# other.net
KiCad netlist of a schematic drawn in Altium Designer
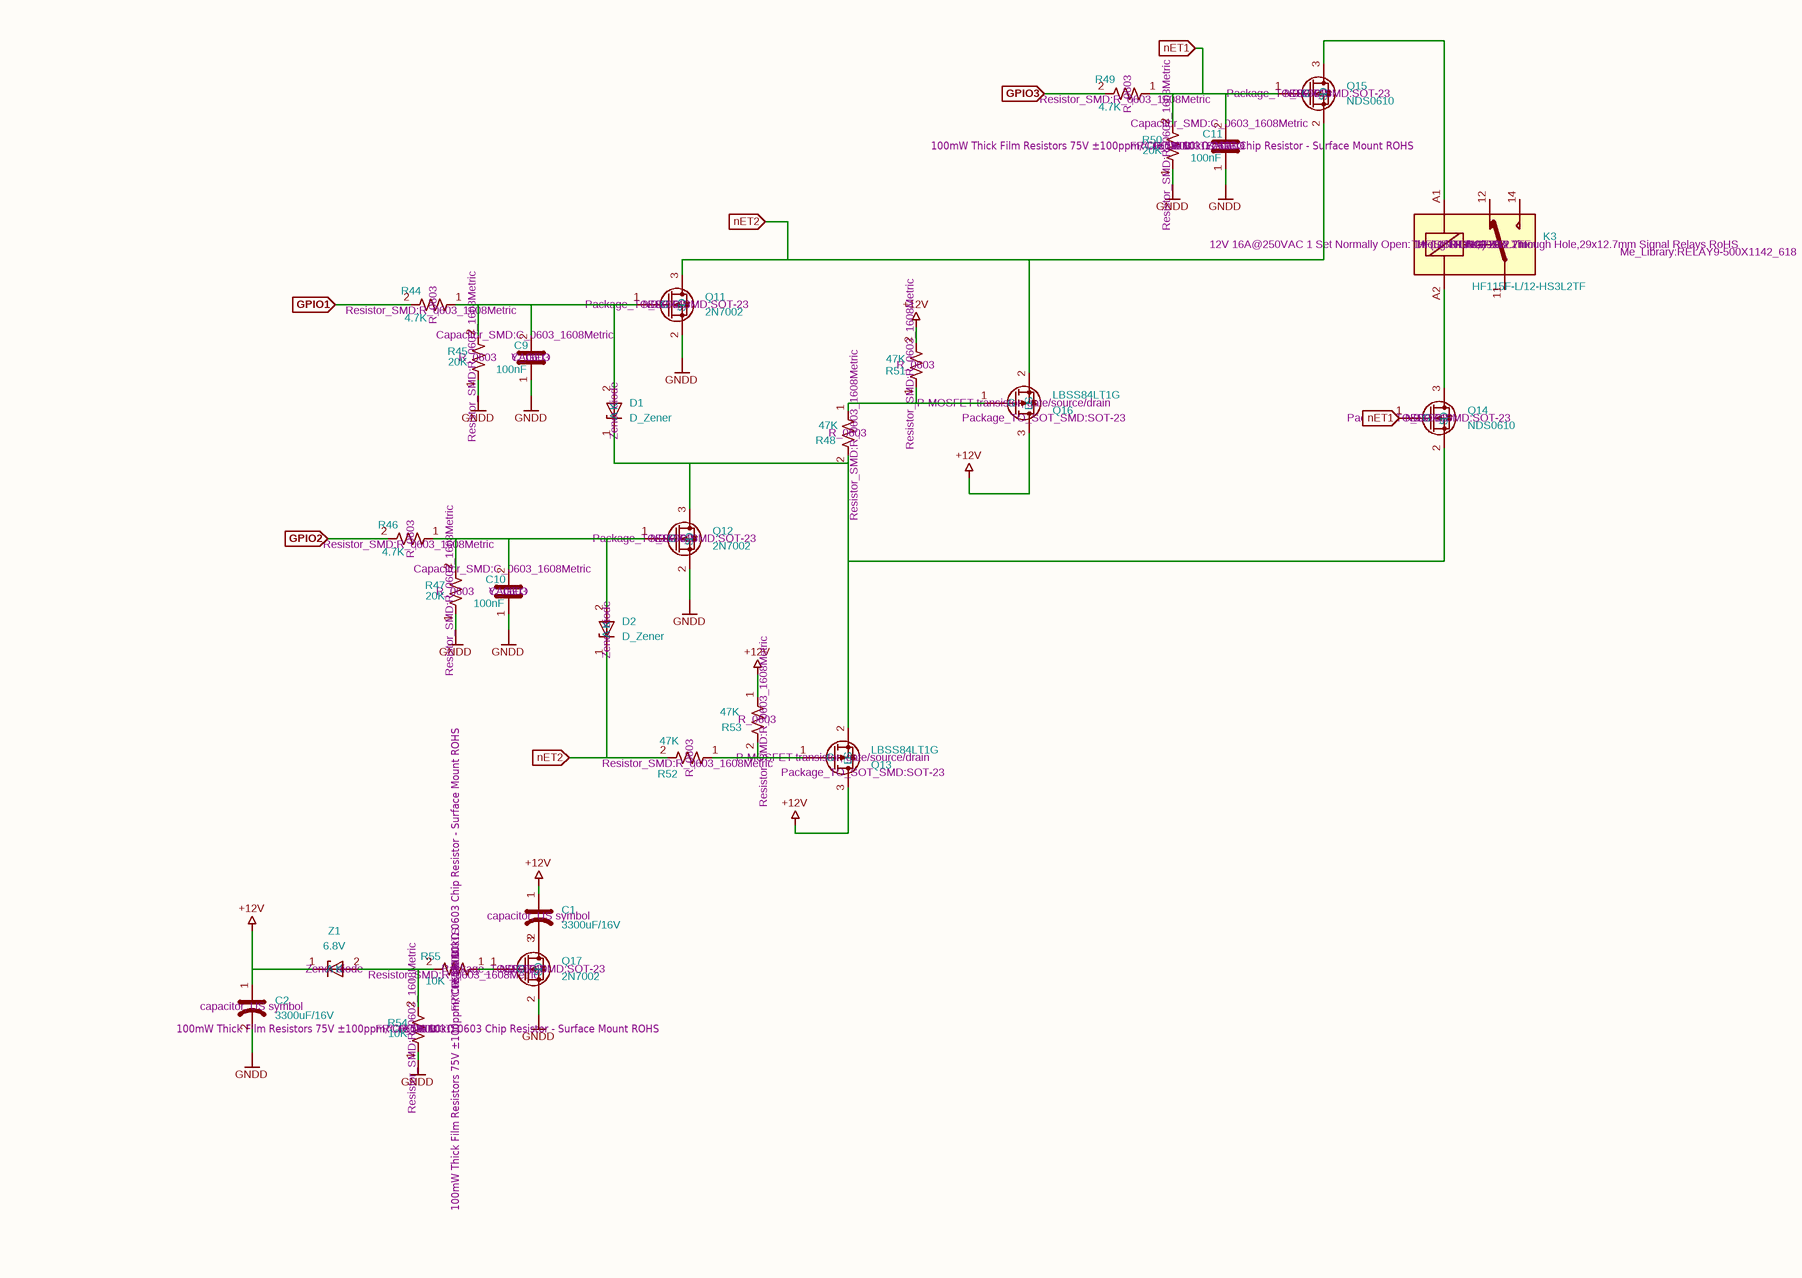
[diagram p0: other.SchDoc, left]
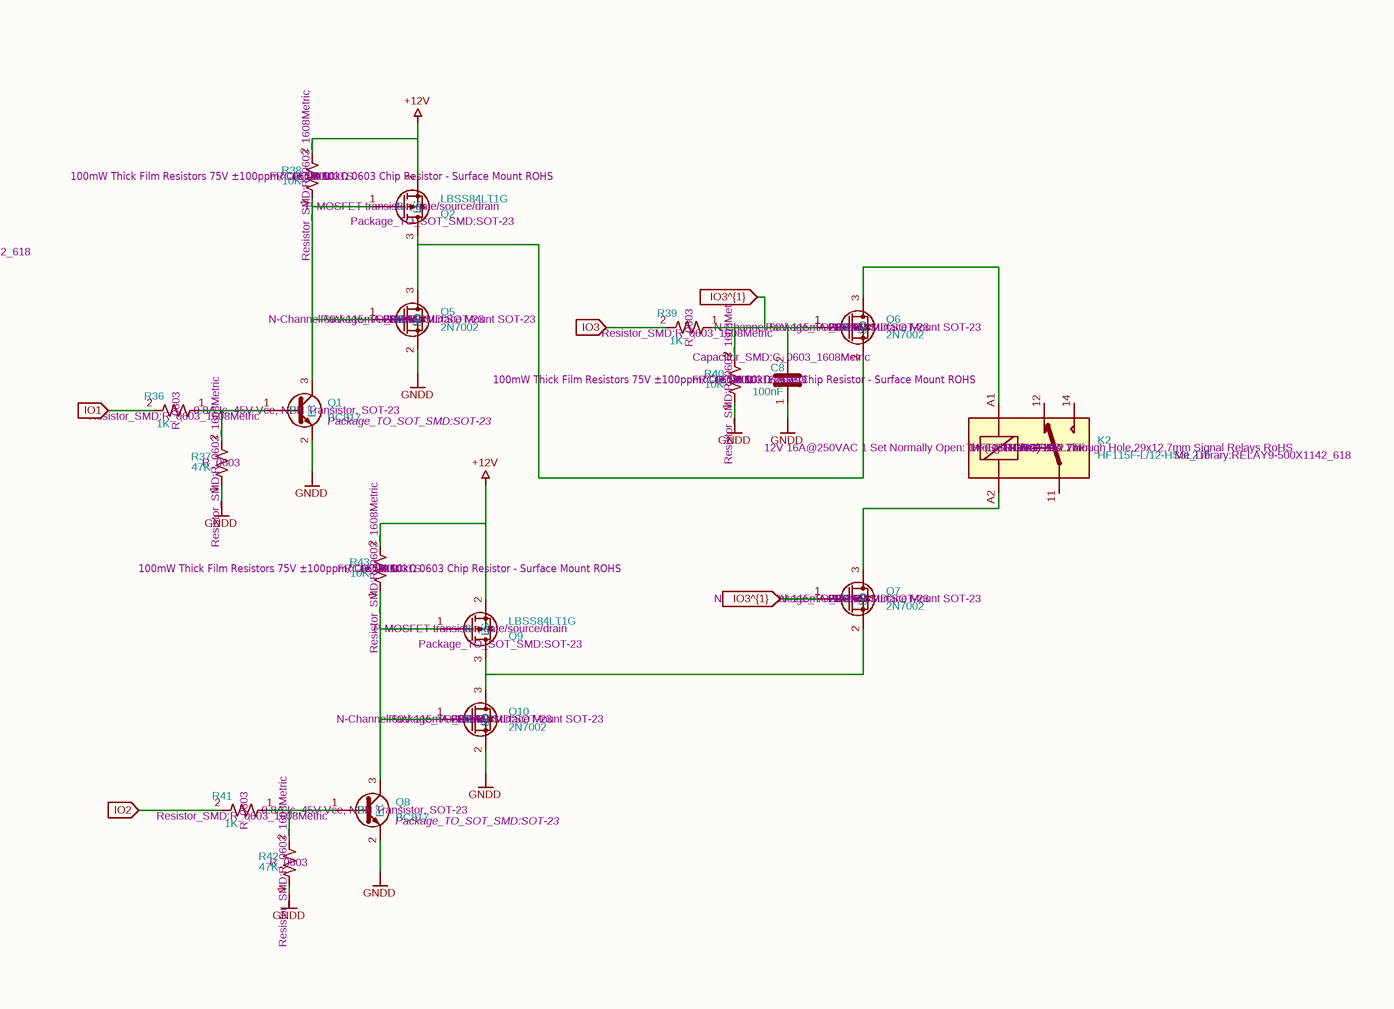
[diagram p1: other.SchDoc, right]

(export (version "E")
  (design (tool "Eeschema 10.0.6"))
  (components
    (comp (ref "C1")
      (value "3300uF/16V")
      (description "capacitor, US symbol")
      (libsource (lib "Device") (part "C_US"))
    )
    (comp (ref "C2")
      (value "3300uF/16V")
      (description "capacitor, US symbol")
      (libsource (lib "Device") (part "C_US"))
    )
    (comp (ref "C8")
      (value "100nF")
      (footprint "Capacitor_SMD:C_0603_1608Metric")
      (fields (field (name "MF") "YAGEO") (field (name "PACKAGE") "C_0603"))
      (libsource (lib "*") (part "C_3"))
    )
    (comp (ref "C9")
      (value "100nF")
      (footprint "Capacitor_SMD:C_0603_1608Metric")
      (fields (field (name "MF") "YAGEO") (field (name "PACKAGE") "C_0603"))
      (libsource (lib "*") (part "C_3"))
    )
    (comp (ref "C10")
      (value "100nF")
      (footprint "Capacitor_SMD:C_0603_1608Metric")
      (fields (field (name "MF") "YAGEO") (field (name "PACKAGE") "C_0603"))
      (libsource (lib "*") (part "C_3"))
    )
    (comp (ref "C11")
      (value "100nF")
      (footprint "Capacitor_SMD:C_0603_1608Metric")
      (fields (field (name "MF") "YAGEO") (field (name "PACKAGE") "C_0603"))
      (libsource (lib "*") (part "C_3"))
    )
    (comp (ref "D1") (value "D_Zener") (description "Zener diode") (libsource (lib "*") (part "D_Zener_1")))
    (comp (ref "D2")
      (value "D_Zener")
      (description "Zener diode")
      (libsource (lib "Device") (part "D_Zener"))
    )
    (comp (ref "K2")
      (value "HF115F-L/12-HS3L2TF")
      (footprint "Me_Library:RELAY9-500X1142_618")
      (description "12V 16A@250VAC 1 Set Normally Open: 1A (SPST NO) 20A Through Hole,29x12.7mm Signal Relays RoHS")
      (fields
        (field (name "MP") "HF115F-L/12-HS3L2TF")
        (field (name "MF") "HONGFA")
        (field (name "PACKAGE") "Through Hole,29x12.7mm")
        (field (name "OZD") "RT314F12")
      )
      (libsource (lib "*") (part "RT314A03_1"))
    )
    (comp (ref "K3")
      (value "HF115F-L/12-HS3L2TF")
      (footprint "Me_Library:RELAY9-500X1142_618")
      (description "12V 16A@250VAC 1 Set Normally Open: 1A (SPST NO) 20A Through Hole,29x12.7mm Signal Relays RoHS")
      (fields
        (field (name "MP") "HF115F-L/12-HS3L2TF")
        (field (name "MF") "HONGFA")
        (field (name "PACKAGE") "Through Hole,29x12.7mm")
        (field (name "OZD") "RT314F12")
      )
      (libsource (lib "*") (part "RT314A03_1"))
    )
    (comp (ref "Q1")
      (value "BC817")
      (footprint "Package_TO_SOT_SMD:SOT-23")
      (description "0.8A Ic, 45V Vce, NPN Transistor, SOT-23")
      (libsource (lib "Transistor_BJT") (part "BC817"))
    )
    (comp (ref "Q2")
      (value "LBSS84LT1G")
      (footprint "Package_TO_SOT_SMD:SOT-23")
      (description "P-MOSFET transistor, gate/source/drain")
      (libsource (lib "Transistor_FET") (part "Q_PMOS_GSD"))
    )
    (comp (ref "Q5")
      (value "2N7002")
      (footprint "Package_TO_SOT_SMD:SOT-23")
      (description "N-Channel 60V 115mA 225mW Surface Mount SOT-23")
      (fields (field (name "MP") "2N7002") (field (name "MF") "FOSAN") (field (name "PACKAGE") "SOT-23"))
      (libsource (lib "Transistor_FET_Other") (part "Q_NMOS_Depletion_GSD"))
    )
    (comp (ref "Q6")
      (value "2N7002")
      (footprint "Package_TO_SOT_SMD:SOT-23")
      (description "N-Channel 60V 115mA 225mW Surface Mount SOT-23")
      (fields (field (name "MP") "2N7002") (field (name "MF") "FOSAN") (field (name "PACKAGE") "SOT-23"))
      (libsource (lib "Transistor_FET_Other") (part "Q_NMOS_Depletion_GSD"))
    )
    (comp (ref "Q7")
      (value "2N7002")
      (footprint "Package_TO_SOT_SMD:SOT-23")
      (description "N-Channel 60V 115mA 225mW Surface Mount SOT-23")
      (fields (field (name "MP") "2N7002") (field (name "MF") "FOSAN") (field (name "PACKAGE") "SOT-23"))
      (libsource (lib "Transistor_FET_Other") (part "Q_NMOS_Depletion_GSD"))
    )
    (comp (ref "Q8")
      (value "BC817")
      (footprint "Package_TO_SOT_SMD:SOT-23")
      (description "0.8A Ic, 45V Vce, NPN Transistor, SOT-23")
      (libsource (lib "Transistor_BJT") (part "BC817"))
    )
    (comp (ref "Q9")
      (value "LBSS84LT1G")
      (footprint "Package_TO_SOT_SMD:SOT-23")
      (description "P-MOSFET transistor, gate/source/drain")
      (libsource (lib "Transistor_FET") (part "Q_PMOS_GSD"))
    )
    (comp (ref "Q10")
      (value "2N7002")
      (footprint "Package_TO_SOT_SMD:SOT-23")
      (description "N-Channel 60V 115mA 225mW Surface Mount SOT-23")
      (fields (field (name "MP") "2N7002") (field (name "MF") "FOSAN") (field (name "PACKAGE") "SOT-23"))
      (libsource (lib "Transistor_FET_Other") (part "Q_NMOS_Depletion_GSD"))
    )
    (comp (ref "Q11")
      (value "2N7002")
      (footprint "Package_TO_SOT_SMD:SOT-23")
      (fields (field (name "MP") "NDS0610") (field (name "PACKAGE") "SOT-23"))
      (libsource (lib "Transistor_FET_Other") (part "Q_NMOS_Depletion_GSD"))
    )
    (comp (ref "Q12")
      (value "2N7002")
      (footprint "Package_TO_SOT_SMD:SOT-23")
      (fields (field (name "MP") "NDS0610") (field (name "PACKAGE") "SOT-23"))
      (libsource (lib "Transistor_FET_Other") (part "Q_NMOS_Depletion_GSD"))
    )
    (comp (ref "Q13")
      (value "LBSS84LT1G")
      (footprint "Package_TO_SOT_SMD:SOT-23")
      (description "P-MOSFET transistor, gate/source/drain")
      (libsource (lib "Transistor_FET") (part "Q_PMOS_GSD"))
    )
    (comp (ref "Q14")
      (value "NDS0610")
      (footprint "Package_TO_SOT_SMD:SOT-23")
      (fields (field (name "MP") "NDS0610") (field (name "PACKAGE") "SOT-23"))
      (libsource (lib "Transistor_FET_Other") (part "Q_NMOS_Depletion_GSD"))
    )
    (comp (ref "Q15")
      (value "NDS0610")
      (footprint "Package_TO_SOT_SMD:SOT-23")
      (fields (field (name "MP") "NDS0610") (field (name "PACKAGE") "SOT-23"))
      (libsource (lib "Transistor_FET_Other") (part "Q_NMOS_Depletion_GSD"))
    )
    (comp (ref "Q16")
      (value "LBSS84LT1G")
      (footprint "Package_TO_SOT_SMD:SOT-23")
      (description "P-MOSFET transistor, gate/source/drain")
      (libsource (lib "*") (part "Q_PMOS_GSD_1"))
    )
    (comp (ref "Q17")
      (value "2N7002")
      (footprint "Package_TO_SOT_SMD:SOT-23")
      (fields (field (name "MP") "NDS0610") (field (name "PACKAGE") "SOT-23"))
      (libsource (lib "Transistor_FET_Other") (part "Q_NMOS_Depletion_GSD"))
    )
    (comp (ref "R36")
      (value "1K")
      (footprint "Resistor_SMD:R_0603_1608Metric")
      (fields (field (name "PACKAGE") "R_0603"))
      (libsource (lib "Device") (part "R_US"))
    )
    (comp (ref "R37")
      (value "47K")
      (footprint "Resistor_SMD:R_0603_1608Metric")
      (fields (field (name "PACKAGE") "R_0603"))
      (libsource (lib "Device") (part "R_US"))
    )
    (comp (ref "R38")
      (value "10K")
      (footprint "Resistor_SMD:R_0603_1608Metric")
      (description "100mW Thick Film Resistors 75V ±100ppm/℃ ±5% 10kΩ 0603 Chip Resistor - Surface Mount ROHS")
      (fields
        (field (name "MP") "FRC0603J103TS")
        (field (name "MF") "FOJAN")
        (field (name "PACKAGE") "R_0603")
      )
      (libsource (lib "Device") (part "R_US"))
    )
    (comp (ref "R39")
      (value "1K")
      (footprint "Resistor_SMD:R_0603_1608Metric")
      (fields (field (name "PACKAGE") "R_0603"))
      (libsource (lib "Device") (part "R_US"))
    )
    (comp (ref "R40")
      (value "10K")
      (footprint "Resistor_SMD:R_0603_1608Metric")
      (description "100mW Thick Film Resistors 75V ±100ppm/℃ ±5% 10kΩ 0603 Chip Resistor - Surface Mount ROHS")
      (fields
        (field (name "MP") "FRC0603J103TS")
        (field (name "MF") "FOJAN")
        (field (name "PACKAGE") "R_0603")
      )
      (libsource (lib "Device") (part "R_US"))
    )
    (comp (ref "R41")
      (value "1K")
      (footprint "Resistor_SMD:R_0603_1608Metric")
      (fields (field (name "PACKAGE") "R_0603"))
      (libsource (lib "Device") (part "R_US"))
    )
    (comp (ref "R42")
      (value "47K")
      (footprint "Resistor_SMD:R_0603_1608Metric")
      (fields (field (name "PACKAGE") "R_0603"))
      (libsource (lib "Device") (part "R_US"))
    )
    (comp (ref "R43")
      (value "10K")
      (footprint "Resistor_SMD:R_0603_1608Metric")
      (description "100mW Thick Film Resistors 75V ±100ppm/℃ ±5% 10kΩ 0603 Chip Resistor - Surface Mount ROHS")
      (fields
        (field (name "MP") "FRC0603J103TS")
        (field (name "MF") "FOJAN")
        (field (name "PACKAGE") "R_0603")
      )
      (libsource (lib "Device") (part "R_US"))
    )
    (comp (ref "R44")
      (value "4.7K")
      (footprint "Resistor_SMD:R_0603_1608Metric")
      (fields (field (name "PACKAGE") "R_0603"))
      (libsource (lib "Device") (part "R_US"))
    )
    (comp (ref "R45")
      (value "20K")
      (footprint "Resistor_SMD:R_0603_1608Metric")
      (fields (field (name "PACKAGE") "R_0603"))
      (libsource (lib "Device") (part "R_US"))
    )
    (comp (ref "R46")
      (value "4.7K")
      (footprint "Resistor_SMD:R_0603_1608Metric")
      (fields (field (name "PACKAGE") "R_0603"))
      (libsource (lib "Device") (part "R_US"))
    )
    (comp (ref "R47")
      (value "20K")
      (footprint "Resistor_SMD:R_0603_1608Metric")
      (fields (field (name "PACKAGE") "R_0603"))
      (libsource (lib "Device") (part "R_US"))
    )
    (comp (ref "R48")
      (value "47K")
      (footprint "Resistor_SMD:R_0603_1608Metric")
      (fields (field (name "PACKAGE") "R_0603"))
      (libsource (lib "Device") (part "R_US"))
    )
    (comp (ref "R49")
      (value "4.7K")
      (footprint "Resistor_SMD:R_0603_1608Metric")
      (fields (field (name "PACKAGE") "R_0603"))
      (libsource (lib "Device") (part "R_US"))
    )
    (comp (ref "R50")
      (value "20K")
      (footprint "Resistor_SMD:R_0603_1608Metric")
      (description "100mW Thick Film Resistors 75V ±100ppm/℃ ±5% 10kΩ 0603 Chip Resistor - Surface Mount ROHS")
      (fields
        (field (name "MP") "FRC0603J103TS")
        (field (name "MF") "FOJAN")
        (field (name "PACKAGE") "R_0603")
      )
      (libsource (lib "Device") (part "R_US"))
    )
    (comp (ref "R51")
      (value "47K")
      (footprint "Resistor_SMD:R_0603_1608Metric")
      (fields (field (name "PACKAGE") "R_0603"))
      (libsource (lib "Device") (part "R_US"))
    )
    (comp (ref "R52")
      (value "47K")
      (footprint "Resistor_SMD:R_0603_1608Metric")
      (fields (field (name "PACKAGE") "R_0603"))
      (libsource (lib "Device") (part "R_US"))
    )
    (comp (ref "R53")
      (value "47K")
      (footprint "Resistor_SMD:R_0603_1608Metric")
      (fields (field (name "PACKAGE") "R_0603"))
      (libsource (lib "Device") (part "R_US"))
    )
    (comp (ref "R54")
      (value "10K")
      (footprint "Resistor_SMD:R_0603_1608Metric")
      (description "100mW Thick Film Resistors 75V ±100ppm/℃ ±5% 10kΩ 0603 Chip Resistor - Surface Mount ROHS")
      (fields
        (field (name "MP") "FRC0603J103TS")
        (field (name "MF") "FOJAN")
        (field (name "PACKAGE") "R_0603")
      )
      (libsource (lib "Device") (part "R_US"))
    )
    (comp (ref "R55")
      (value "10K")
      (footprint "Resistor_SMD:R_0603_1608Metric")
      (description "100mW Thick Film Resistors 75V ±100ppm/℃ ±5% 10kΩ 0603 Chip Resistor - Surface Mount ROHS")
      (fields
        (field (name "MP") "FRC0603J103TS")
        (field (name "MF") "FOJAN")
        (field (name "PACKAGE") "R_0603")
      )
      (libsource (lib "Device") (part "R_US"))
    )
    (comp (ref "Z1") (value "6.8V") (description "Zener diode") (libsource (lib "Device") (part "D_Zener")))
  )
  (nets
    (net (code "1") (name "+12V") (class "Default")
      (node (ref "C1") (pin "1") (pinfunction "1_1") (pintype "passive"))
      (node (ref "C2") (pin "1") (pinfunction "1_1") (pintype "passive"))
      (node (ref "Q13") (pin "3") (pinfunction "D_3") (pintype "passive"))
      (node (ref "Q16") (pin "3") (pinfunction "D_3") (pintype "passive"))
      (node (ref "Q2") (pin "2") (pinfunction "S_2") (pintype "passive"))
      (node (ref "Q9") (pin "2") (pinfunction "S_2") (pintype "passive"))
      (node (ref "R38") (pin "2") (pinfunction "2_2") (pintype "passive"))
      (node (ref "R43") (pin "2") (pinfunction "2_2") (pintype "passive"))
      (node (ref "R51") (pin "2") (pinfunction "2_2") (pintype "passive"))
      (node (ref "R53") (pin "1") (pinfunction "1_1") (pintype "passive"))
      (node (ref "Z1") (pin "1") (pinfunction "K_1") (pintype "passive"))
    )
    (net (code "2") (name "/GPIO1") (class "Default")
      (node (ref "R44") (pin "2") (pinfunction "2_2") (pintype "passive"))
    )
    (net (code "3") (name "/GPIO2") (class "Default")
      (node (ref "R46") (pin "2") (pinfunction "2_2") (pintype "passive"))
    )
    (net (code "4") (name "/GPIO3") (class "Default")
      (node (ref "R49") (pin "2") (pinfunction "2_2") (pintype "passive"))
    )
    (net (code "5") (name "/IO1") (class "Default")
      (node (ref "R36") (pin "2") (pinfunction "2_2") (pintype "passive"))
    )
    (net (code "6") (name "/IO2") (class "Default")
      (node (ref "R41") (pin "2") (pinfunction "2_2") (pintype "passive"))
    )
    (net (code "7") (name "/IO3") (class "Default")
      (node (ref "R39") (pin "2") (pinfunction "2_2") (pintype "passive"))
    )
    (net (code "8") (name "/IO3^{1}") (class "Default")
      (node (ref "C8") (pin "2") (pinfunction "2_2") (pintype "passive"))
      (node (ref "Q6") (pin "1") (pinfunction "G_1") (pintype "passive"))
      (node (ref "Q7") (pin "1") (pinfunction "G_1") (pintype "passive"))
      (node (ref "R39") (pin "1") (pinfunction "1_1") (pintype "passive"))
      (node (ref "R40") (pin "2") (pinfunction "2_2") (pintype "passive"))
    )
    (net (code "9") (name "/nET1") (class "Default")
      (node (ref "C11") (pin "2") (pinfunction "2_2") (pintype "passive"))
      (node (ref "Q14") (pin "1") (pinfunction "G_1") (pintype "passive"))
      (node (ref "Q15") (pin "1") (pinfunction "G_1") (pintype "passive"))
      (node (ref "R49") (pin "1") (pinfunction "1_1") (pintype "passive"))
      (node (ref "R50") (pin "2") (pinfunction "2_2") (pintype "passive"))
    )
    (net (code "10") (name "/nET2") (class "Default")
      (node (ref "D2") (pin "1") (pinfunction "K_1") (pintype "passive"))
      (node (ref "Q11") (pin "3") (pinfunction "D_3") (pintype "passive"))
      (node (ref "Q15") (pin "2") (pinfunction "S_2") (pintype "passive"))
      (node (ref "Q16") (pin "2") (pinfunction "S_2") (pintype "passive"))
      (node (ref "R52") (pin "2") (pinfunction "2_2") (pintype "passive"))
    )
    (net (code "11") (name "GNDD") (class "Default")
      (node (ref "C10") (pin "1") (pinfunction "1_1") (pintype "passive"))
      (node (ref "C11") (pin "1") (pinfunction "1_1") (pintype "passive"))
      (node (ref "C2") (pin "2") (pinfunction "2_2") (pintype "passive"))
      (node (ref "C8") (pin "1") (pinfunction "1_1") (pintype "passive"))
      (node (ref "C9") (pin "1") (pinfunction "1_1") (pintype "passive"))
      (node (ref "Q1") (pin "2") (pinfunction "E_2") (pintype "passive"))
      (node (ref "Q10") (pin "2") (pinfunction "S_2") (pintype "passive"))
      (node (ref "Q11") (pin "2") (pinfunction "S_2") (pintype "passive"))
      (node (ref "Q12") (pin "2") (pinfunction "S_2") (pintype "passive"))
      (node (ref "Q17") (pin "2") (pinfunction "S_2") (pintype "passive"))
      (node (ref "Q5") (pin "2") (pinfunction "S_2") (pintype "passive"))
      (node (ref "Q8") (pin "2") (pinfunction "E_2") (pintype "passive"))
      (node (ref "R37") (pin "1") (pinfunction "1_1") (pintype "passive"))
      (node (ref "R40") (pin "1") (pinfunction "1_1") (pintype "passive"))
      (node (ref "R42") (pin "1") (pinfunction "1_1") (pintype "passive"))
      (node (ref "R45") (pin "1") (pinfunction "1_1") (pintype "passive"))
      (node (ref "R47") (pin "1") (pinfunction "1_1") (pintype "passive"))
      (node (ref "R50") (pin "1") (pinfunction "1_1") (pintype "passive"))
      (node (ref "R54") (pin "1") (pinfunction "1_1") (pintype "passive"))
    )
    (net (code "12") (name "Net-(D1-A)") (class "Default")
      (node (ref "C9") (pin "2") (pinfunction "2_2") (pintype "passive"))
      (node (ref "D1") (pin "2") (pinfunction "A_2") (pintype "passive"))
      (node (ref "Q11") (pin "1") (pinfunction "G_1") (pintype "passive"))
      (node (ref "R44") (pin "1") (pinfunction "1_1") (pintype "passive"))
      (node (ref "R45") (pin "2") (pinfunction "2_2") (pintype "passive"))
    )
    (net (code "13") (name "Net-(D1-K)") (class "Default")
      (node (ref "D1") (pin "1") (pinfunction "K_1") (pintype "passive"))
      (node (ref "Q12") (pin "3") (pinfunction "D_3") (pintype "passive"))
      (node (ref "Q13") (pin "2") (pinfunction "S_2") (pintype "passive"))
      (node (ref "Q14") (pin "2") (pinfunction "S_2") (pintype "passive"))
      (node (ref "R48") (pin "2") (pinfunction "2_2") (pintype "passive"))
    )
    (net (code "14") (name "Net-(D2-A)") (class "Default")
      (node (ref "C10") (pin "2") (pinfunction "2_2") (pintype "passive"))
      (node (ref "D2") (pin "2") (pinfunction "A_2") (pintype "passive"))
      (node (ref "Q12") (pin "1") (pinfunction "G_1") (pintype "passive"))
      (node (ref "R46") (pin "1") (pinfunction "1_1") (pintype "passive"))
      (node (ref "R47") (pin "2") (pinfunction "2_2") (pintype "passive"))
    )
    (net (code "15") (name "Net-(Q1-B)") (class "Default")
      (node (ref "Q1") (pin "1") (pinfunction "B_1") (pintype "passive"))
      (node (ref "R36") (pin "1") (pinfunction "1_1") (pintype "passive"))
      (node (ref "R37") (pin "2") (pinfunction "2_2") (pintype "passive"))
    )
    (net (code "16") (name "Net-(Q1-C)") (class "Default")
      (node (ref "Q1") (pin "3") (pinfunction "C_3") (pintype "passive"))
      (node (ref "Q2") (pin "1") (pinfunction "G_1") (pintype "passive"))
      (node (ref "Q5") (pin "1") (pinfunction "G_1") (pintype "passive"))
      (node (ref "R38") (pin "1") (pinfunction "1_1") (pintype "passive"))
    )
    (net (code "17") (name "Net-(Q2-D)") (class "Default")
      (node (ref "Q2") (pin "3") (pinfunction "D_3") (pintype "passive"))
      (node (ref "Q5") (pin "3") (pinfunction "D_3") (pintype "passive"))
      (node (ref "Q6") (pin "2") (pinfunction "S_2") (pintype "passive"))
    )
    (net (code "18") (name "Net-(Q6-D)") (class "Default")
      (node (ref "K2") (pin "A1") (pinfunction "A1_A1") (pintype "passive"))
      (node (ref "Q6") (pin "3") (pinfunction "D_3") (pintype "passive"))
    )
    (net (code "19") (name "Net-(Q7-D)") (class "Default")
      (node (ref "K2") (pin "A2") (pinfunction "A2_A2") (pintype "passive"))
      (node (ref "Q7") (pin "3") (pinfunction "D_3") (pintype "passive"))
    )
    (net (code "20") (name "Net-(Q8-B)") (class "Default")
      (node (ref "Q8") (pin "1") (pinfunction "B_1") (pintype "passive"))
      (node (ref "R41") (pin "1") (pinfunction "1_1") (pintype "passive"))
      (node (ref "R42") (pin "2") (pinfunction "2_2") (pintype "passive"))
    )
    (net (code "21") (name "Net-(Q10-D)") (class "Default")
      (node (ref "Q10") (pin "3") (pinfunction "D_3") (pintype "passive"))
      (node (ref "Q7") (pin "2") (pinfunction "S_2") (pintype "passive"))
      (node (ref "Q9") (pin "3") (pinfunction "D_3") (pintype "passive"))
    )
    (net (code "22") (name "Net-(Q10-G)") (class "Default")
      (node (ref "Q10") (pin "1") (pinfunction "G_1") (pintype "passive"))
      (node (ref "Q8") (pin "3") (pinfunction "C_3") (pintype "passive"))
      (node (ref "Q9") (pin "1") (pinfunction "G_1") (pintype "passive"))
      (node (ref "R43") (pin "1") (pinfunction "1_1") (pintype "passive"))
    )
    (net (code "23") (name "Net-(Q13-G)") (class "Default")
      (node (ref "Q13") (pin "1") (pinfunction "G_1") (pintype "passive"))
      (node (ref "R52") (pin "1") (pinfunction "1_1") (pintype "passive"))
      (node (ref "R53") (pin "2") (pinfunction "2_2") (pintype "passive"))
    )
    (net (code "24") (name "Net-(Q14-D)") (class "Default")
      (node (ref "K3") (pin "A2") (pinfunction "A2_A2") (pintype "passive"))
      (node (ref "Q14") (pin "3") (pinfunction "D_3") (pintype "passive"))
    )
    (net (code "25") (name "Net-(Q15-D)") (class "Default")
      (node (ref "K3") (pin "A1") (pinfunction "A1_A1") (pintype "passive"))
      (node (ref "Q15") (pin "3") (pinfunction "D_3") (pintype "passive"))
    )
    (net (code "26") (name "Net-(Q16-G)") (class "Default")
      (node (ref "Q16") (pin "1") (pinfunction "G_1") (pintype "passive"))
      (node (ref "R48") (pin "1") (pinfunction "1_1") (pintype "passive"))
      (node (ref "R51") (pin "1") (pinfunction "1_1") (pintype "passive"))
    )
    (net (code "27") (name "Net-(Q17-D)") (class "Default")
      (node (ref "C1") (pin "2") (pinfunction "2_2") (pintype "passive"))
      (node (ref "Q17") (pin "3") (pinfunction "D_3") (pintype "passive"))
    )
    (net (code "28") (name "Net-(Q17-G)") (class "Default")
      (node (ref "Q17") (pin "1") (pinfunction "G_1") (pintype "passive"))
      (node (ref "R55") (pin "1") (pinfunction "1_1") (pintype "passive"))
    )
    (net (code "29") (name "Net-(Z1-A)") (class "Default")
      (node (ref "R54") (pin "2") (pinfunction "2_2") (pintype "passive"))
      (node (ref "R55") (pin "2") (pinfunction "2_2") (pintype "passive"))
      (node (ref "Z1") (pin "2") (pinfunction "A_2") (pintype "passive"))
    )
    (net (code "30") (name "unconnected-(K2-Pad11)") (class "Default")
      (node (ref "K2") (pin "11") (pinfunction "11_11") (pintype "passive"))
    )
    (net (code "31") (name "unconnected-(K2-Pad12)") (class "Default")
      (node (ref "K2") (pin "12") (pinfunction "12_12") (pintype "passive"))
    )
    (net (code "32") (name "unconnected-(K2-Pad14)") (class "Default")
      (node (ref "K2") (pin "14") (pinfunction "14_14") (pintype "passive"))
    )
    (net (code "33") (name "unconnected-(K3-Pad11)") (class "Default")
      (node (ref "K3") (pin "11") (pinfunction "11_11") (pintype "passive"))
    )
    (net (code "34") (name "unconnected-(K3-Pad12)") (class "Default")
      (node (ref "K3") (pin "12") (pinfunction "12_12") (pintype "passive"))
    )
    (net (code "35") (name "unconnected-(K3-Pad14)") (class "Default")
      (node (ref "K3") (pin "14") (pinfunction "14_14") (pintype "passive"))
    )
  )
)
